# Qduino_Mini.net
KiCad netlist of a schematic drawn in EAGLE
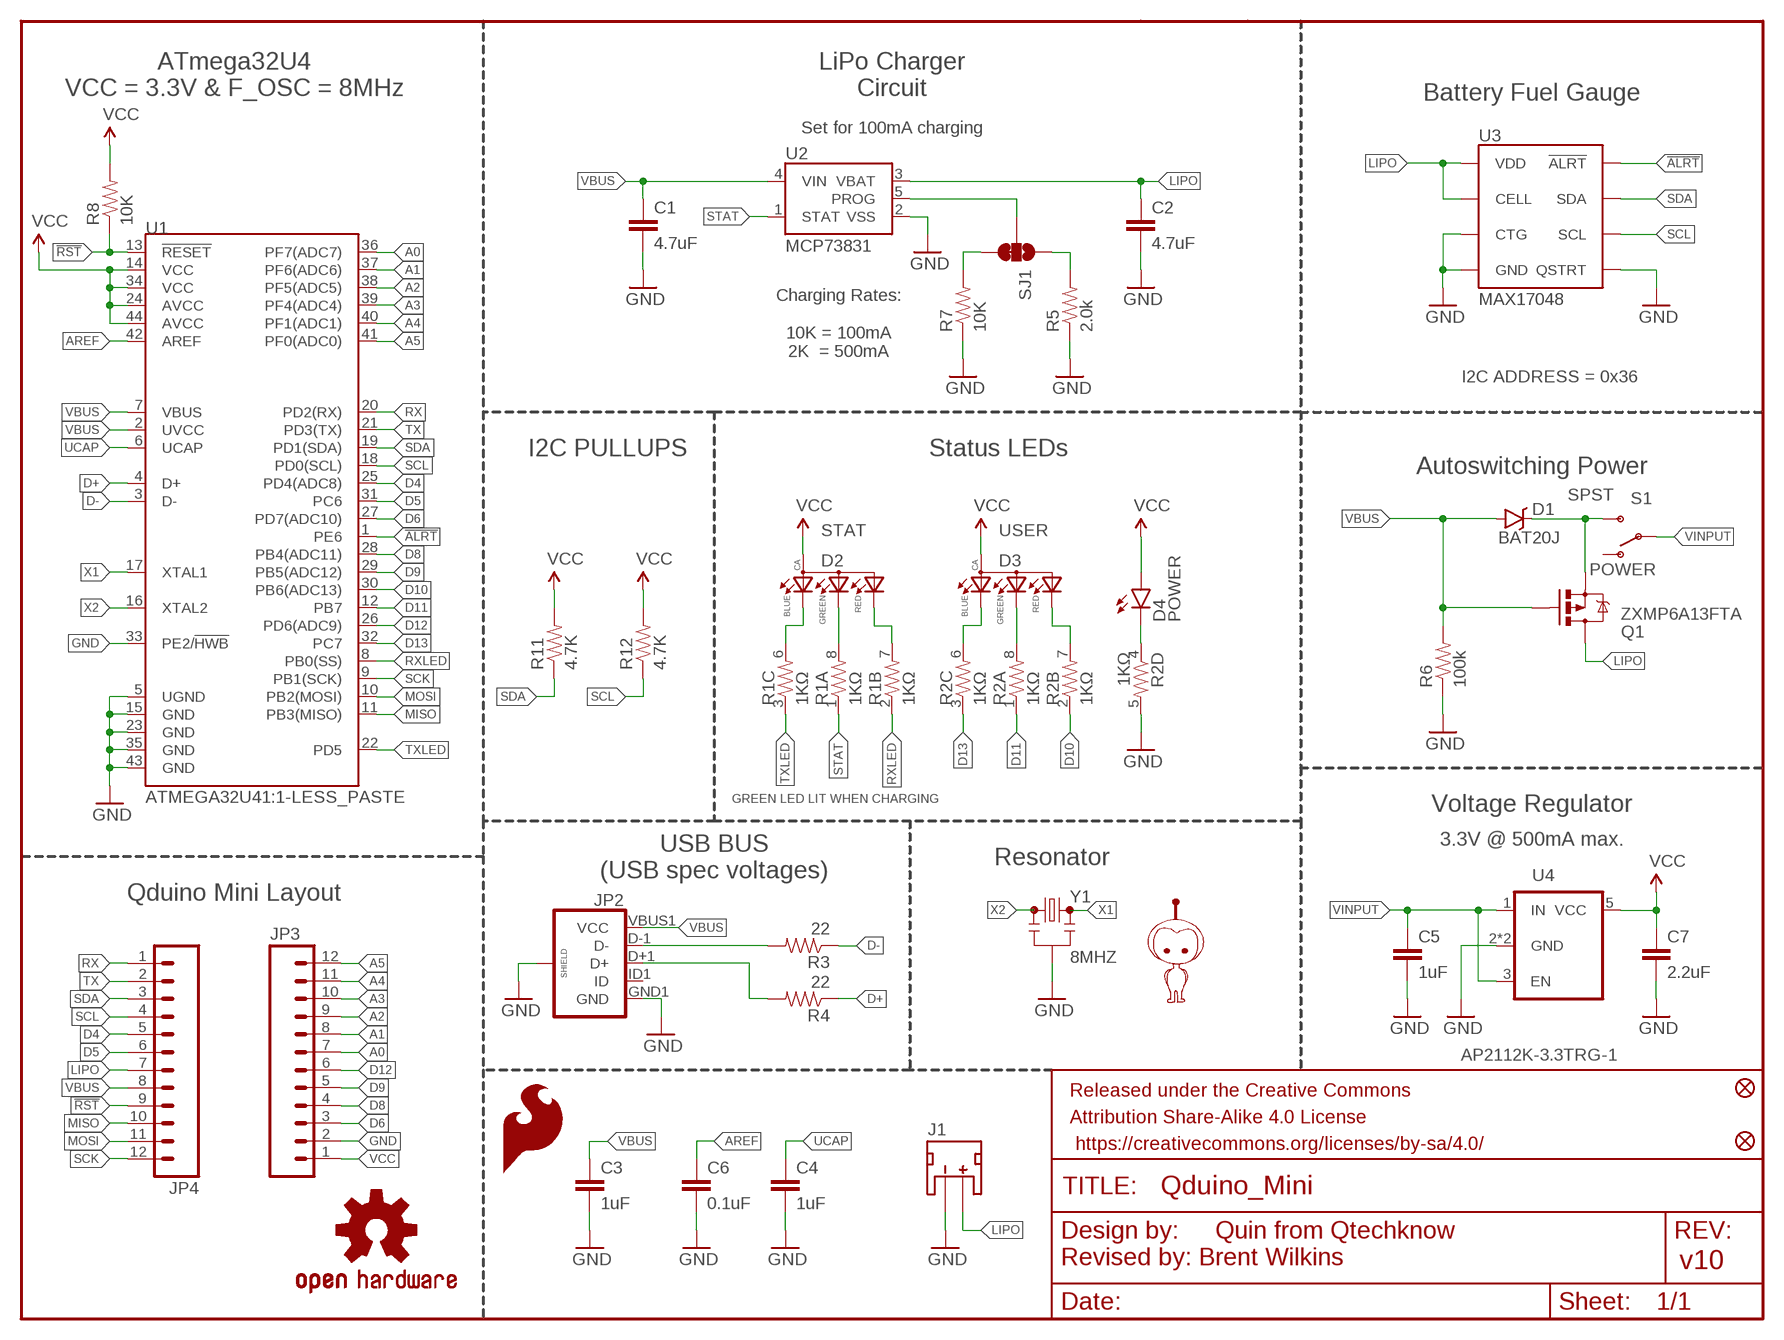
[diagram p0: schematic, sheet 1]

(export (version "E")
  (design (tool "Eeschema 10.0.6"))
  (components
    (comp (ref "C1")
      (value "4.7uF")
      (footprint "eagle-import:0603-CAP")
      (libsource (lib "eagle-import") (part "CAP0603-CAP"))
    )
    (comp (ref "C2")
      (value "4.7uF")
      (footprint "eagle-import:0603-CAP")
      (libsource (lib "eagle-import") (part "CAP0603-CAP"))
    )
    (comp (ref "C3")
      (value "1uF")
      (footprint "eagle-import:0603-CAP")
      (libsource (lib "eagle-import") (part "CAP0603-CAP"))
    )
    (comp (ref "C4")
      (value "1uF")
      (footprint "eagle-import:0603-CAP")
      (libsource (lib "eagle-import") (part "CAP0603-CAP"))
    )
    (comp (ref "C5")
      (value "1uF")
      (footprint "eagle-import:0603-CAP")
      (libsource (lib "eagle-import") (part "CAP0603-CAP"))
    )
    (comp (ref "C6")
      (value "0.1uF")
      (footprint "eagle-import:0603-CAP")
      (libsource (lib "eagle-import") (part "0.1UF-25V(+80/-20%)(0603)"))
    )
    (comp (ref "C7")
      (value "2.2uF")
      (footprint "eagle-import:0603-CAP")
      (libsource (lib "eagle-import") (part "2.2UF-10V-20%(0603)"))
    )
    (comp (ref "D1")
      (value "BAT20J")
      (footprint "eagle-import:SOD-323")
      (libsource (lib "eagle-import") (part "DIODE-SCHOTTKY-BAT20J"))
    )
    (comp (ref "D2")
      (value "0.13_RGB_LEDPLCC")
      (footprint "eagle-import:P-LCC-4-3")
      (fields (field (name "PROD_ID") "DIO-12986"))
      (libsource (lib "eagle-import") (part "0.13_RGB_LEDPLCC"))
    )
    (comp (ref "D3")
      (value "0.13_RGB_LEDPLCC")
      (footprint "eagle-import:P-LCC-4-3")
      (libsource (lib "eagle-import") (part "0.13_RGB_LEDPLCC"))
    )
    (comp (ref "D4")
      (value "POWER")
      (footprint "eagle-import:LED-0603")
      (fields (field (name "PROD_ID") "DIO-00821"))
      (libsource (lib "eagle-import") (part "LED-GREEN0603"))
    )
    (comp (ref "FID1")
      (value "FIDUCIALUFIDUCIAL")
      (footprint "eagle-import:MICRO-FIDUCIAL")
      (libsource (lib "eagle-import") (part "FIDUCIALUFIDUCIAL"))
    )
    (comp (ref "FID2")
      (value "FIDUCIALUFIDUCIAL")
      (footprint "eagle-import:MICRO-FIDUCIAL")
      (libsource (lib "eagle-import") (part "FIDUCIALUFIDUCIAL"))
    )
    (comp (ref "FRAME2")
      (value "FRAME-LETTER")
      (footprint "eagle-import:CREATIVE_COMMONS")
      (fields (field (name "DESIGNER") "NAME"))
      (libsource (lib "eagle-import") (part "FRAME-LETTER"))
    )
    (comp (ref "J1")
      (value "LiPo")
      (footprint "eagle-import:JST-2-SMD")
      (libsource (lib "eagle-import") (part "JST_2MM_MALE"))
    )
    (comp (ref "JP2")
      (value "USB_MICROB_PLUGCONN-11752")
      (footprint "eagle-import:USB-B-MICRO-SMD_V03")
      (libsource (lib "eagle-import") (part "USB_MICROB_PLUGCONN-11752"))
    )
    (comp (ref "JP3")
      (value "M12PTH")
      (footprint "eagle-import:1X12")
      (libsource (lib "eagle-import") (part "M12PTH"))
    )
    (comp (ref "JP4")
      (value "M12PTH")
      (footprint "eagle-import:1X12")
      (libsource (lib "eagle-import") (part "M12PTH"))
    )
    (comp (ref "LOGO1")
      (value "OSHW-LOGOS")
      (footprint "eagle-import:OSHW-LOGO-S")
      (libsource (lib "eagle-import") (part "OSHW-LOGOS"))
    )
    (comp (ref "LOGO2")
      (value "SFE_LOGO_FLAME.1_INCH")
      (footprint "eagle-import:SFE_LOGO_FLAME_.1")
      (libsource (lib "eagle-import") (part "SFE_LOGO_FLAME.1_INCH"))
    )
    (comp (ref "Q1")
      (value "ZXMP6A13FTA")
      (footprint "eagle-import:SOT23-3")
      (libsource (lib "eagle-import") (part "MOSFET-PCHANNEL"))
    )
    (comp (ref "R1")
      (value "1KΩ")
      (footprint "eagle-import:0603-ARV")
      (fields (field (name "PROD_ID") "RES-12985"))
      (libsource (lib "eagle-import") (part "RESISTOR-ARRAY0603-ARV"))
    )
    (comp (ref "R2")
      (value "1KΩ")
      (footprint "eagle-import:0603-ARV")
      (fields (field (name "PROD_ID") "RES-12985"))
      (libsource (lib "eagle-import") (part "RESISTOR-ARRAY0603-ARV"))
    )
    (comp (ref "R3")
      (value "22")
      (footprint "eagle-import:0603-RES")
      (libsource (lib "eagle-import") (part "RESISTOR0603"))
    )
    (comp (ref "R4")
      (value "22")
      (footprint "eagle-import:0603-RES")
      (libsource (lib "eagle-import") (part "RESISTOR0603"))
    )
    (comp (ref "R5")
      (value "2.0k")
      (footprint "eagle-import:0603-RES")
      (libsource (lib "eagle-import") (part "2.0KOHM1/10W5%(0603)"))
    )
    (comp (ref "R6")
      (value "100k")
      (footprint "eagle-import:0603-RES")
      (libsource (lib "eagle-import") (part "100KOHM-1/10W-1%(0603)"))
    )
    (comp (ref "R7")
      (value "10K")
      (footprint "eagle-import:0603-RES")
      (libsource (lib "eagle-import") (part "10KOHM-1/10W-1%(0603)0603"))
    )
    (comp (ref "R8")
      (value "10K")
      (footprint "eagle-import:0603-RES")
      (libsource (lib "eagle-import") (part "10KOHM-1/10W-1%(0603)0603"))
    )
    (comp (ref "R11")
      (value "4.7K")
      (footprint "eagle-import:0603-RES")
      (libsource (lib "eagle-import") (part "RESISTOR0603-RES"))
    )
    (comp (ref "R12")
      (value "4.7K")
      (footprint "eagle-import:0603-RES")
      (libsource (lib "eagle-import") (part "RESISTOR0603-RES"))
    )
    (comp (ref "S1")
      (value "POWER")
      (footprint "eagle-import:SWITCH-SPST-SMD-A")
      (libsource (lib "eagle-import") (part "SWITCH-SPDT-SMD-A"))
    )
    (comp (ref "SJ1")
      (value "JUMPER-PAD-3-2OF3_NC_BY_TRACE_SMALL")
      (footprint "eagle-import:PAD-JUMPER-3-2OF3_NC_BY_TRACE_YES_SILK_FULL_BOX")
      (libsource (lib "eagle-import") (part "JUMPER-PAD-3-2OF3_NC_BY_TRACE_SMALL"))
    )
    (comp (ref "U1")
      (value "ATMEGA32U41:1-LESS_PASTE")
      (footprint "eagle-import:QFN-44-NOPAD_1_1-LESS_PASTE")
      (libsource (lib "eagle-import") (part "ATMEGA32U41{colon}1-LESS_PASTE"))
    )
    (comp (ref "U2")
      (value "MCP73831")
      (footprint "eagle-import:SOT23-5")
      (libsource (lib "eagle-import") (part "MCP73831"))
    )
    (comp (ref "U3")
      (value "MAX17048")
      (footprint "eagle-import:DFN-8")
      (libsource (lib "eagle-import") (part "MAX17048DFN8"))
    )
    (comp (ref "U4")
      (value "AP2112K-3.3TRG-1")
      (footprint "eagle-import:SOT23-5")
      (libsource (lib "eagle-import") (part "LDO-TPS78233"))
    )
    (comp (ref "U5")
      (value "MIGHTYQ-L-SILK")
      (footprint "eagle-import:LOGO-LARGE-SILK")
      (libsource (lib "eagle-import") (part "MIGHTYQ-L-SILK"))
    )
    (comp (ref "Y1")
      (value "8MHZ")
      (footprint "eagle-import:RESONATOR-SMD")
      (libsource (lib "eagle-import") (part "RESONATOR8MHZ"))
    )
  )
  (nets
    (net (code "1") (name "/~{ALRT}") (class "Default")
      (node (ref "U1") (pin "1") (pinfunction "PE6_1") (pintype "bidirectional"))
      (node (ref "U3") (pin "P$5") (pinfunction "~{ALRT}_P$5") (pintype "bidirectional"))
    )
    (net (code "2") (name "/~{RST}") (class "Default")
      (node (ref "JP4") (pin "9") (pinfunction "9_9") (pintype "passive"))
      (node (ref "R8") (pin "1") (pinfunction "1_1") (pintype "passive"))
      (node (ref "U1") (pin "13") (pinfunction "~{RESET}_13") (pintype "bidirectional"))
    )
    (net (code "3") (name "A0") (class "Default")
      (node (ref "JP3") (pin "7") (pinfunction "7_7") (pintype "passive"))
      (node (ref "U1") (pin "36") (pinfunction "PF7(ADC7)_36") (pintype "bidirectional"))
    )
    (net (code "4") (name "A1") (class "Default")
      (node (ref "JP3") (pin "8") (pinfunction "8_8") (pintype "passive"))
      (node (ref "U1") (pin "37") (pinfunction "PF6(ADC6)_37") (pintype "bidirectional"))
    )
    (net (code "5") (name "A2") (class "Default")
      (node (ref "JP3") (pin "9") (pinfunction "9_9") (pintype "passive"))
      (node (ref "U1") (pin "38") (pinfunction "PF5(ADC5)_38") (pintype "bidirectional"))
    )
    (net (code "6") (name "A3") (class "Default")
      (node (ref "JP3") (pin "10") (pinfunction "10_10") (pintype "passive"))
      (node (ref "U1") (pin "39") (pinfunction "PF4(ADC4)_39") (pintype "bidirectional"))
    )
    (net (code "7") (name "A4") (class "Default")
      (node (ref "JP3") (pin "11") (pinfunction "11_11") (pintype "passive"))
      (node (ref "U1") (pin "40") (pinfunction "PF1(ADC1)_40") (pintype "bidirectional"))
    )
    (net (code "8") (name "A5") (class "Default")
      (node (ref "JP3") (pin "12") (pinfunction "12_12") (pintype "passive"))
      (node (ref "U1") (pin "41") (pinfunction "PF0(ADC0)_41") (pintype "bidirectional"))
    )
    (net (code "9") (name "AREF") (class "Default")
      (node (ref "C6") (pin "1") (pinfunction "1_1") (pintype "passive"))
      (node (ref "U1") (pin "42") (pinfunction "AREF_42") (pintype "bidirectional"))
    )
    (net (code "10") (name "D+") (class "Default")
      (node (ref "R4") (pin "1") (pinfunction "1_1") (pintype "passive"))
      (node (ref "U1") (pin "4") (pinfunction "D+_4") (pintype "bidirectional"))
    )
    (net (code "11") (name "D-") (class "Default")
      (node (ref "R3") (pin "1") (pinfunction "1_1") (pintype "passive"))
      (node (ref "U1") (pin "3") (pinfunction "D-_3") (pintype "bidirectional"))
    )
    (net (code "12") (name "D4") (class "Default")
      (node (ref "JP4") (pin "5") (pinfunction "5_5") (pintype "passive"))
      (node (ref "U1") (pin "25") (pinfunction "PD4(ADC8)_25") (pintype "bidirectional"))
    )
    (net (code "13") (name "D5") (class "Default")
      (node (ref "JP4") (pin "6") (pinfunction "6_6") (pintype "passive"))
      (node (ref "U1") (pin "31") (pinfunction "PC6_31") (pintype "bidirectional"))
    )
    (net (code "14") (name "D6") (class "Default")
      (node (ref "JP3") (pin "3") (pinfunction "3_3") (pintype "passive"))
      (node (ref "U1") (pin "27") (pinfunction "PD7(ADC10)_27") (pintype "bidirectional"))
    )
    (net (code "15") (name "D8") (class "Default")
      (node (ref "JP3") (pin "4") (pinfunction "4_4") (pintype "passive"))
      (node (ref "U1") (pin "28") (pinfunction "PB4(ADC11)_28") (pintype "bidirectional"))
    )
    (net (code "16") (name "D9") (class "Default")
      (node (ref "JP3") (pin "5") (pinfunction "5_5") (pintype "passive"))
      (node (ref "U1") (pin "29") (pinfunction "PB5(ADC12)_29") (pintype "bidirectional"))
    )
    (net (code "17") (name "D10") (class "Default")
      (node (ref "R2") (pin "2") (pinfunction "1_2") (pintype "passive"))
      (node (ref "U1") (pin "30") (pinfunction "PB6(ADC13)_30") (pintype "bidirectional"))
    )
    (net (code "18") (name "D11") (class "Default")
      (node (ref "R2") (pin "1") (pinfunction "1_1") (pintype "passive"))
      (node (ref "U1") (pin "12") (pinfunction "PB7_12") (pintype "bidirectional"))
    )
    (net (code "19") (name "D12") (class "Default")
      (node (ref "JP3") (pin "6") (pinfunction "6_6") (pintype "passive"))
      (node (ref "U1") (pin "26") (pinfunction "PD6(ADC9)_26") (pintype "bidirectional"))
    )
    (net (code "20") (name "D13") (class "Default")
      (node (ref "R2") (pin "3") (pinfunction "1_3") (pintype "passive"))
      (node (ref "U1") (pin "32") (pinfunction "PC7_32") (pintype "bidirectional"))
    )
    (net (code "21") (name "GND") (class "Default")
      (node (ref "C1") (pin "2") (pinfunction "2_2") (pintype "passive"))
      (node (ref "C2") (pin "2") (pinfunction "2_2") (pintype "passive"))
      (node (ref "C3") (pin "2") (pinfunction "2_2") (pintype "passive"))
      (node (ref "C4") (pin "2") (pinfunction "2_2") (pintype "passive"))
      (node (ref "C5") (pin "2") (pinfunction "2_2") (pintype "passive"))
      (node (ref "C6") (pin "2") (pinfunction "2_2") (pintype "passive"))
      (node (ref "C7") (pin "2") (pinfunction "2_2") (pintype "passive"))
      (node (ref "J1") (pin "1") (pinfunction "-_1") (pintype "bidirectional"))
      (node (ref "JP2") (pin "GND1") (pinfunction "GND_GND1") (pintype "bidirectional"))
      (node (ref "JP2") (pin "SHIELD1") (pinfunction "SHIELD_SHIELD1") (pintype "bidirectional"))
      (node (ref "JP2") (pin "SHIELD2") (pinfunction "SHIELD_SHIELD2") (pintype "bidirectional"))
      (node (ref "JP2") (pin "SHIELD3") (pinfunction "SHIELD_SHIELD3") (pintype "bidirectional"))
      (node (ref "JP3") (pin "2") (pinfunction "2_2") (pintype "passive"))
      (node (ref "R2") (pin "5") (pinfunction "2_5") (pintype "passive"))
      (node (ref "R5") (pin "1") (pinfunction "1_1") (pintype "passive"))
      (node (ref "R6") (pin "1") (pinfunction "1_1") (pintype "passive"))
      (node (ref "R7") (pin "1") (pinfunction "1_1") (pintype "passive"))
      (node (ref "U1") (pin "15") (pinfunction "GND_15") (pintype "bidirectional"))
      (node (ref "U1") (pin "23") (pinfunction "GND_23") (pintype "bidirectional"))
      (node (ref "U1") (pin "33") (pinfunction "PE2/~{HWB}_33") (pintype "bidirectional"))
      (node (ref "U1") (pin "35") (pinfunction "GND_35") (pintype "bidirectional"))
      (node (ref "U1") (pin "43") (pinfunction "GND_43") (pintype "bidirectional"))
      (node (ref "U1") (pin "5") (pinfunction "UGND_5") (pintype "bidirectional"))
      (node (ref "U2") (pin "2") (pinfunction "VSS_2") (pintype "power_in"))
      (node (ref "U3") (pin "P$1") (pinfunction "CTG_P$1") (pintype "input"))
      (node (ref "U3") (pin "P$4") (pinfunction "GND_P$4") (pintype "bidirectional"))
      (node (ref "U3") (pin "P$6") (pinfunction "QSTRT_P$6") (pintype "bidirectional"))
      (node (ref "U3") (pin "P$9") (pinfunction "GND_P$9") (pintype "bidirectional"))
      (node (ref "U4") (pin "2") (pinfunction "GND_2") (pintype "input"))
      (node (ref "U4") (pin "4") (pinfunction "GND_4") (pintype "input"))
      (node (ref "Y1") (pin "2") (pinfunction "2_2") (pintype "passive"))
    )
    (net (code "22") (name "LIPO") (class "Default")
      (node (ref "C2") (pin "1") (pinfunction "1_1") (pintype "passive"))
      (node (ref "J1") (pin "2") (pinfunction "+_2") (pintype "bidirectional"))
      (node (ref "JP4") (pin "7") (pinfunction "7_7") (pintype "passive"))
      (node (ref "Q1") (pin "3") (pinfunction "D_3") (pintype "passive"))
      (node (ref "U2") (pin "3") (pinfunction "VBAT_3") (pintype "power_in"))
      (node (ref "U3") (pin "P$2") (pinfunction "CELL_P$2") (pintype "input"))
      (node (ref "U3") (pin "P$3") (pinfunction "VDD_P$3") (pintype "bidirectional"))
    )
    (net (code "23") (name "MISO") (class "Default")
      (node (ref "JP4") (pin "10") (pinfunction "10_10") (pintype "passive"))
      (node (ref "U1") (pin "11") (pinfunction "PB3(MISO)_11") (pintype "bidirectional"))
    )
    (net (code "24") (name "MOSI") (class "Default")
      (node (ref "JP4") (pin "11") (pinfunction "11_11") (pintype "passive"))
      (node (ref "U1") (pin "10") (pinfunction "PB2(MOSI)_10") (pintype "bidirectional"))
    )
    (net (code "25") (name "Net-(D2-BLUE)") (class "Default")
      (node (ref "D2") (pin "3") (pinfunction "BLUE_3") (pintype "passive"))
      (node (ref "R1") (pin "6") (pinfunction "2_6") (pintype "passive"))
    )
    (net (code "26") (name "Net-(D2-GREEN)") (class "Default")
      (node (ref "D2") (pin "2") (pinfunction "GREEN_2") (pintype "passive"))
      (node (ref "R1") (pin "8") (pinfunction "2_8") (pintype "passive"))
    )
    (net (code "27") (name "Net-(D2-RED)") (class "Default")
      (node (ref "D2") (pin "1") (pinfunction "RED_1") (pintype "passive"))
      (node (ref "R1") (pin "7") (pinfunction "2_7") (pintype "passive"))
    )
    (net (code "28") (name "Net-(D3-BLUE)") (class "Default")
      (node (ref "D3") (pin "3") (pinfunction "BLUE_3") (pintype "passive"))
      (node (ref "R2") (pin "6") (pinfunction "2_6") (pintype "passive"))
    )
    (net (code "29") (name "Net-(D3-GREEN)") (class "Default")
      (node (ref "D3") (pin "2") (pinfunction "GREEN_2") (pintype "passive"))
      (node (ref "R2") (pin "8") (pinfunction "2_8") (pintype "passive"))
    )
    (net (code "30") (name "Net-(D3-RED)") (class "Default")
      (node (ref "D3") (pin "1") (pinfunction "RED_1") (pintype "passive"))
      (node (ref "R2") (pin "7") (pinfunction "2_7") (pintype "passive"))
    )
    (net (code "31") (name "Net-(JP2-D+)") (class "Default")
      (node (ref "JP2") (pin "D+1") (pinfunction "D+_D+1") (pintype "bidirectional"))
      (node (ref "R4") (pin "2") (pinfunction "2_2") (pintype "passive"))
    )
    (net (code "32") (name "Net-(JP2-D-)") (class "Default")
      (node (ref "JP2") (pin "D-1") (pinfunction "D-_D-1") (pintype "bidirectional"))
      (node (ref "R3") (pin "2") (pinfunction "2_2") (pintype "passive"))
    )
    (net (code "33") (name "Net-(Q1-S)") (class "Default")
      (node (ref "D1") (pin "C") (pinfunction "C_C") (pintype "passive"))
      (node (ref "Q1") (pin "2") (pinfunction "S_2") (pintype "passive"))
      (node (ref "S1") (pin "3") (pinfunction "S_3") (pintype "passive"))
    )
    (net (code "34") (name "Net-(R2D-1)") (class "Default")
      (node (ref "D4") (pin "C") (pinfunction "C_C") (pintype "passive"))
      (node (ref "R2") (pin "4") (pinfunction "1_4") (pintype "passive"))
    )
    (net (code "35") (name "Net-(R5-Pad2)") (class "Default")
      (node (ref "R5") (pin "2") (pinfunction "2_2") (pintype "passive"))
      (node (ref "SJ1") (pin "1") (pinfunction "1_1") (pintype "passive"))
    )
    (net (code "36") (name "Net-(R7-Pad2)") (class "Default")
      (node (ref "R7") (pin "2") (pinfunction "2_2") (pintype "passive"))
      (node (ref "SJ1") (pin "3") (pinfunction "3_3") (pintype "passive"))
    )
    (net (code "37") (name "Net-(U2-PROG)") (class "Default")
      (node (ref "SJ1") (pin "2") (pinfunction "2_2") (pintype "passive"))
      (node (ref "U2") (pin "5") (pinfunction "PROG_5") (pintype "input"))
    )
    (net (code "38") (name "RX") (class "Default")
      (node (ref "JP4") (pin "1") (pinfunction "1_1") (pintype "passive"))
      (node (ref "U1") (pin "20") (pinfunction "PD2(RX)_20") (pintype "bidirectional"))
    )
    (net (code "39") (name "RXLED") (class "Default")
      (node (ref "R1") (pin "2") (pinfunction "1_2") (pintype "passive"))
      (node (ref "U1") (pin "8") (pinfunction "PB0(SS)_8") (pintype "bidirectional"))
    )
    (net (code "40") (name "SCK") (class "Default")
      (node (ref "JP4") (pin "12") (pinfunction "12_12") (pintype "passive"))
      (node (ref "U1") (pin "9") (pinfunction "PB1(SCK)_9") (pintype "bidirectional"))
    )
    (net (code "41") (name "SCL") (class "Default")
      (node (ref "JP4") (pin "4") (pinfunction "4_4") (pintype "passive"))
      (node (ref "R12") (pin "1") (pinfunction "1_1") (pintype "passive"))
      (node (ref "U1") (pin "18") (pinfunction "PD0(SCL)_18") (pintype "bidirectional"))
      (node (ref "U3") (pin "P$7") (pinfunction "SCL_P$7") (pintype "output"))
    )
    (net (code "42") (name "SDA") (class "Default")
      (node (ref "JP4") (pin "3") (pinfunction "3_3") (pintype "passive"))
      (node (ref "R11") (pin "1") (pinfunction "1_1") (pintype "passive"))
      (node (ref "U1") (pin "19") (pinfunction "PD1(SDA)_19") (pintype "bidirectional"))
      (node (ref "U3") (pin "P$8") (pinfunction "SDA_P$8") (pintype "input"))
    )
    (net (code "43") (name "STAT") (class "Default")
      (node (ref "R1") (pin "1") (pinfunction "1_1") (pintype "passive"))
      (node (ref "U2") (pin "1") (pinfunction "STAT_1") (pintype "output"))
    )
    (net (code "44") (name "TX") (class "Default")
      (node (ref "JP4") (pin "2") (pinfunction "2_2") (pintype "passive"))
      (node (ref "U1") (pin "21") (pinfunction "PD3(TX)_21") (pintype "bidirectional"))
    )
    (net (code "45") (name "TXLED") (class "Default")
      (node (ref "R1") (pin "3") (pinfunction "1_3") (pintype "passive"))
      (node (ref "U1") (pin "22") (pinfunction "PD5_22") (pintype "bidirectional"))
    )
    (net (code "46") (name "UCAP") (class "Default")
      (node (ref "C4") (pin "1") (pinfunction "1_1") (pintype "passive"))
      (node (ref "U1") (pin "6") (pinfunction "UCAP_6") (pintype "bidirectional"))
    )
    (net (code "47") (name "VBUS") (class "Default")
      (node (ref "C1") (pin "1") (pinfunction "1_1") (pintype "passive"))
      (node (ref "C3") (pin "1") (pinfunction "1_1") (pintype "passive"))
      (node (ref "D1") (pin "A") (pinfunction "A_A") (pintype "passive"))
      (node (ref "JP2") (pin "VBUS1") (pinfunction "VCC_VBUS1") (pintype "bidirectional"))
      (node (ref "JP4") (pin "8") (pinfunction "8_8") (pintype "passive"))
      (node (ref "Q1") (pin "1") (pinfunction "G_1") (pintype "passive"))
      (node (ref "R6") (pin "2") (pinfunction "2_2") (pintype "passive"))
      (node (ref "U1") (pin "2") (pinfunction "UVCC_2") (pintype "bidirectional"))
      (node (ref "U1") (pin "7") (pinfunction "VBUS_7") (pintype "bidirectional"))
      (node (ref "U2") (pin "4") (pinfunction "VIN_4") (pintype "power_in"))
    )
    (net (code "48") (name "VCC") (class "Default")
      (node (ref "C7") (pin "1") (pinfunction "1_1") (pintype "passive"))
      (node (ref "D2") (pin "4") (pinfunction "ANODE_4") (pintype "passive"))
      (node (ref "D3") (pin "4") (pinfunction "ANODE_4") (pintype "passive"))
      (node (ref "D4") (pin "A") (pinfunction "A_A") (pintype "passive"))
      (node (ref "JP3") (pin "1") (pinfunction "1_1") (pintype "passive"))
      (node (ref "R11") (pin "2") (pinfunction "2_2") (pintype "passive"))
      (node (ref "R12") (pin "2") (pinfunction "2_2") (pintype "passive"))
      (node (ref "R8") (pin "2") (pinfunction "2_2") (pintype "passive"))
      (node (ref "U1") (pin "14") (pinfunction "VCC_14") (pintype "bidirectional"))
      (node (ref "U1") (pin "24") (pinfunction "AVCC_24") (pintype "bidirectional"))
      (node (ref "U1") (pin "34") (pinfunction "VCC_34") (pintype "bidirectional"))
      (node (ref "U1") (pin "44") (pinfunction "AVCC_44") (pintype "bidirectional"))
      (node (ref "U4") (pin "5") (pinfunction "VCC_5") (pintype "power_in"))
    )
    (net (code "49") (name "VINPUT") (class "Default")
      (node (ref "C5") (pin "1") (pinfunction "1_1") (pintype "passive"))
      (node (ref "S1") (pin "2") (pinfunction "P_2") (pintype "passive"))
      (node (ref "U4") (pin "1") (pinfunction "IN_1") (pintype "input"))
      (node (ref "U4") (pin "3") (pinfunction "EN_3") (pintype "input"))
    )
    (net (code "50") (name "X1") (class "Default")
      (node (ref "U1") (pin "17") (pinfunction "XTAL1_17") (pintype "bidirectional"))
      (node (ref "Y1") (pin "3") (pinfunction "3_3") (pintype "passive"))
    )
    (net (code "51") (name "X2") (class "Default")
      (node (ref "U1") (pin "16") (pinfunction "XTAL2_16") (pintype "bidirectional"))
      (node (ref "Y1") (pin "1") (pinfunction "1_1") (pintype "passive"))
    )
    (net (code "52") (name "unconnected-(J1-PAD1-PadNC1)") (class "Default")
      (node (ref "J1") (pin "NC1") (pinfunction "PAD1_NC1") (pintype "bidirectional"))
    )
    (net (code "53") (name "unconnected-(J1-PAD2-PadNC2)") (class "Default")
      (node (ref "J1") (pin "NC2") (pinfunction "PAD2_NC2") (pintype "bidirectional"))
    )
    (net (code "54") (name "unconnected-(JP2-ID-PadID1)") (class "Default")
      (node (ref "JP2") (pin "ID1") (pinfunction "ID_ID1") (pintype "bidirectional"))
    )
    (net (code "55") (name "unconnected-(S1-O-Pad1)") (class "Default")
      (node (ref "S1") (pin "1") (pinfunction "O_1") (pintype "passive"))
    )
  )
)
